# shield.net
KiCad netlist of a schematic drawn in EAGLE
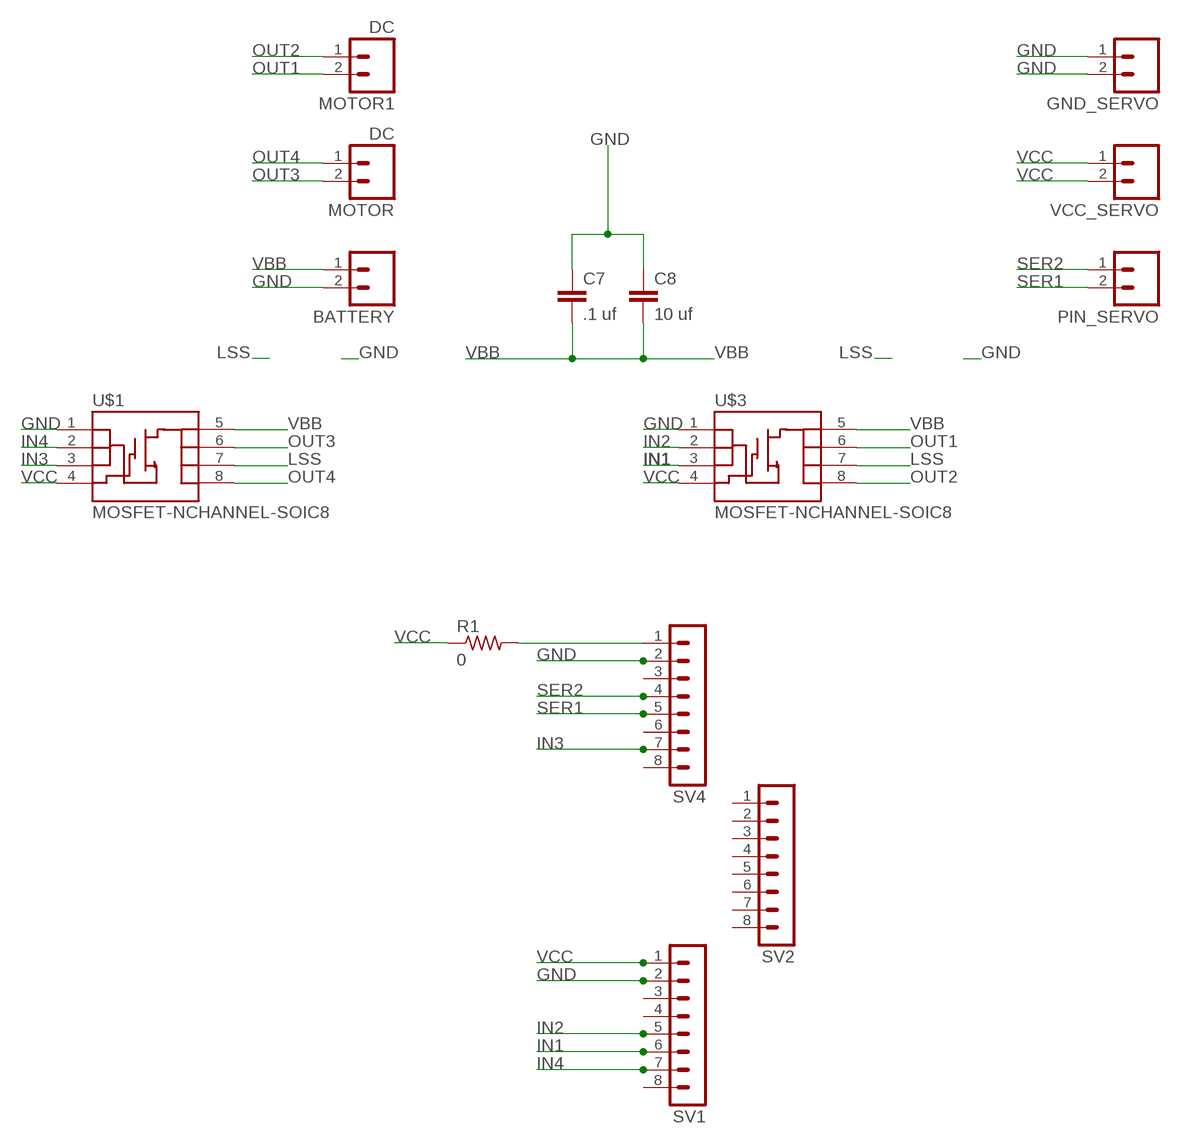
[diagram p0: schematic, sheet 1]

(export (version "E")
  (design (tool "Eeschema 10.0.6"))
  (components
    (comp (ref "BATTERY")
      (value "M02")
      (footprint "eagle-import:1X02_LONGPADS")
      (libsource (lib "eagle-import") (part "M02"))
    )
    (comp (ref "C7")
      (value ".1 uf")
      (footprint "eagle-import:1206")
      (libsource (lib "eagle-import") (part "CAP1206"))
    )
    (comp (ref "C8")
      (value "10 uf")
      (footprint "eagle-import:1206")
      (libsource (lib "eagle-import") (part "CAP1206"))
    )
    (comp (ref "GND_SERVO")
      (value "M02")
      (footprint "eagle-import:1X02_LONGPADS")
      (libsource (lib "eagle-import") (part "M02"))
    )
    (comp (ref "MOTOR")
      (value "DC")
      (footprint "eagle-import:1X02_LONGPADS")
      (libsource (lib "eagle-import") (part "M02"))
    )
    (comp (ref "MOTOR1")
      (value "DC")
      (footprint "eagle-import:1X02_LONGPADS")
      (libsource (lib "eagle-import") (part "M02"))
    )
    (comp (ref "PIN_SERVO")
      (value "M02")
      (footprint "eagle-import:1X02_LONGPADS")
      (libsource (lib "eagle-import") (part "M02"))
    )
    (comp (ref "R1")
      (value "0")
      (footprint "eagle-import:1206")
      (libsource (lib "eagle-import") (part "RESISTOR1206"))
    )
    (comp (ref "SV1")
      (value "MA08-1")
      (footprint "eagle-import:MA08-1")
      (libsource (lib "eagle-import") (part "MA08-1"))
    )
    (comp (ref "SV2")
      (value "MA08-1")
      (footprint "eagle-import:MA08-1")
      (libsource (lib "eagle-import") (part "MA08-1"))
    )
    (comp (ref "SV4")
      (value "MA08-1")
      (footprint "eagle-import:MA08-1")
      (libsource (lib "eagle-import") (part "MA08-1"))
    )
    (comp (ref "U$1")
      (value "MOSFET-NCHANNEL-SOIC8")
      (footprint "eagle-import:SO08")
      (libsource (lib "eagle-import") (part "MOSFET-NCHANNEL-SOIC8"))
    )
    (comp (ref "U$3")
      (value "MOSFET-NCHANNEL-SOIC8")
      (footprint "eagle-import:SO08")
      (libsource (lib "eagle-import") (part "MOSFET-NCHANNEL-SOIC8"))
    )
    (comp (ref "VCC_SERVO")
      (value "M02")
      (footprint "eagle-import:1X02_LONGPADS")
      (libsource (lib "eagle-import") (part "M02"))
    )
  )
  (nets
    (net (code "1") (name "/GND") (class "Default")
      (node (ref "BATTERY") (pin "2") (pinfunction "2_2") (pintype "passive"))
      (node (ref "C7") (pin "1") (pinfunction "1_1") (pintype "passive"))
      (node (ref "C8") (pin "1") (pinfunction "1_1") (pintype "passive"))
      (node (ref "GND_SERVO") (pin "1") (pinfunction "1_1") (pintype "passive"))
      (node (ref "GND_SERVO") (pin "2") (pinfunction "2_2") (pintype "passive"))
      (node (ref "SV1") (pin "2") (pinfunction "2_2") (pintype "passive"))
      (node (ref "SV4") (pin "2") (pinfunction "2_2") (pintype "passive"))
      (node (ref "U$1") (pin "1") (pinfunction "S_1") (pintype "bidirectional"))
      (node (ref "U$3") (pin "1") (pinfunction "S_1") (pintype "bidirectional"))
    )
    (net (code "2") (name "/IN1") (class "Default")
      (node (ref "SV1") (pin "6") (pinfunction "6_6") (pintype "passive"))
      (node (ref "U$3") (pin "3") (pinfunction "S_3") (pintype "bidirectional"))
    )
    (net (code "3") (name "/IN2") (class "Default")
      (node (ref "SV1") (pin "5") (pinfunction "5_5") (pintype "passive"))
      (node (ref "U$3") (pin "2") (pinfunction "S_2") (pintype "bidirectional"))
    )
    (net (code "4") (name "/IN3") (class "Default")
      (node (ref "SV4") (pin "7") (pinfunction "7_7") (pintype "passive"))
      (node (ref "U$1") (pin "3") (pinfunction "S_3") (pintype "bidirectional"))
    )
    (net (code "5") (name "/IN4") (class "Default")
      (node (ref "SV1") (pin "7") (pinfunction "7_7") (pintype "passive"))
      (node (ref "U$1") (pin "2") (pinfunction "S_2") (pintype "bidirectional"))
    )
    (net (code "6") (name "/LSS") (class "Default")
      (node (ref "U$1") (pin "7") (pinfunction "D_7") (pintype "bidirectional"))
      (node (ref "U$3") (pin "7") (pinfunction "D_7") (pintype "bidirectional"))
    )
    (net (code "7") (name "/OUT1") (class "Default")
      (node (ref "MOTOR1") (pin "2") (pinfunction "2_2") (pintype "passive"))
      (node (ref "U$3") (pin "6") (pinfunction "D_6") (pintype "bidirectional"))
    )
    (net (code "8") (name "/OUT2") (class "Default")
      (node (ref "MOTOR1") (pin "1") (pinfunction "1_1") (pintype "passive"))
      (node (ref "U$3") (pin "8") (pinfunction "D_8") (pintype "bidirectional"))
    )
    (net (code "9") (name "/OUT3") (class "Default")
      (node (ref "MOTOR") (pin "2") (pinfunction "2_2") (pintype "passive"))
      (node (ref "U$1") (pin "6") (pinfunction "D_6") (pintype "bidirectional"))
    )
    (net (code "10") (name "/OUT4") (class "Default")
      (node (ref "MOTOR") (pin "1") (pinfunction "1_1") (pintype "passive"))
      (node (ref "U$1") (pin "8") (pinfunction "D_8") (pintype "bidirectional"))
    )
    (net (code "11") (name "/SER1") (class "Default")
      (node (ref "PIN_SERVO") (pin "2") (pinfunction "2_2") (pintype "passive"))
      (node (ref "SV4") (pin "5") (pinfunction "5_5") (pintype "passive"))
    )
    (net (code "12") (name "/SER2") (class "Default")
      (node (ref "PIN_SERVO") (pin "1") (pinfunction "1_1") (pintype "passive"))
      (node (ref "SV4") (pin "4") (pinfunction "4_4") (pintype "passive"))
    )
    (net (code "13") (name "/VBB") (class "Default")
      (node (ref "BATTERY") (pin "1") (pinfunction "1_1") (pintype "passive"))
      (node (ref "C7") (pin "2") (pinfunction "2_2") (pintype "passive"))
      (node (ref "C8") (pin "2") (pinfunction "2_2") (pintype "passive"))
      (node (ref "U$1") (pin "5") (pinfunction "D_5") (pintype "bidirectional"))
      (node (ref "U$3") (pin "5") (pinfunction "D_5") (pintype "bidirectional"))
    )
    (net (code "14") (name "/VCC") (class "Default")
      (node (ref "R1") (pin "1") (pinfunction "1_1") (pintype "passive"))
      (node (ref "SV1") (pin "1") (pinfunction "1_1") (pintype "passive"))
      (node (ref "U$1") (pin "4") (pinfunction "G_4") (pintype "bidirectional"))
      (node (ref "U$3") (pin "4") (pinfunction "G_4") (pintype "bidirectional"))
      (node (ref "VCC_SERVO") (pin "1") (pinfunction "1_1") (pintype "passive"))
      (node (ref "VCC_SERVO") (pin "2") (pinfunction "2_2") (pintype "passive"))
    )
    (net (code "15") (name "Net-(R1-Pad2)") (class "Default")
      (node (ref "R1") (pin "2") (pinfunction "2_2") (pintype "passive"))
      (node (ref "SV4") (pin "1") (pinfunction "1_1") (pintype "passive"))
    )
    (net (code "16") (name "unconnected-(SV1-Pad3)") (class "Default")
      (node (ref "SV1") (pin "3") (pinfunction "3_3") (pintype "passive"))
    )
    (net (code "17") (name "unconnected-(SV1-Pad4)") (class "Default")
      (node (ref "SV1") (pin "4") (pinfunction "4_4") (pintype "passive"))
    )
    (net (code "18") (name "unconnected-(SV1-Pad8)") (class "Default")
      (node (ref "SV1") (pin "8") (pinfunction "8_8") (pintype "passive"))
    )
    (net (code "19") (name "unconnected-(SV2-Pad1)") (class "Default")
      (node (ref "SV2") (pin "1") (pinfunction "1_1") (pintype "passive"))
    )
    (net (code "20") (name "unconnected-(SV2-Pad2)") (class "Default")
      (node (ref "SV2") (pin "2") (pinfunction "2_2") (pintype "passive"))
    )
    (net (code "21") (name "unconnected-(SV2-Pad3)") (class "Default")
      (node (ref "SV2") (pin "3") (pinfunction "3_3") (pintype "passive"))
    )
    (net (code "22") (name "unconnected-(SV2-Pad4)") (class "Default")
      (node (ref "SV2") (pin "4") (pinfunction "4_4") (pintype "passive"))
    )
    (net (code "23") (name "unconnected-(SV2-Pad5)") (class "Default")
      (node (ref "SV2") (pin "5") (pinfunction "5_5") (pintype "passive"))
    )
    (net (code "24") (name "unconnected-(SV2-Pad6)") (class "Default")
      (node (ref "SV2") (pin "6") (pinfunction "6_6") (pintype "passive"))
    )
    (net (code "25") (name "unconnected-(SV2-Pad7)") (class "Default")
      (node (ref "SV2") (pin "7") (pinfunction "7_7") (pintype "passive"))
    )
    (net (code "26") (name "unconnected-(SV2-Pad8)") (class "Default")
      (node (ref "SV2") (pin "8") (pinfunction "8_8") (pintype "passive"))
    )
    (net (code "27") (name "unconnected-(SV4-Pad3)") (class "Default")
      (node (ref "SV4") (pin "3") (pinfunction "3_3") (pintype "passive"))
    )
    (net (code "28") (name "unconnected-(SV4-Pad6)") (class "Default")
      (node (ref "SV4") (pin "6") (pinfunction "6_6") (pintype "passive"))
    )
    (net (code "29") (name "unconnected-(SV4-Pad8)") (class "Default")
      (node (ref "SV4") (pin "8") (pinfunction "8_8") (pintype "passive"))
    )
  )
)
